# 12V_Buck_LDO_Power.net
KiCad netlist of a schematic drawn in Altium Designer
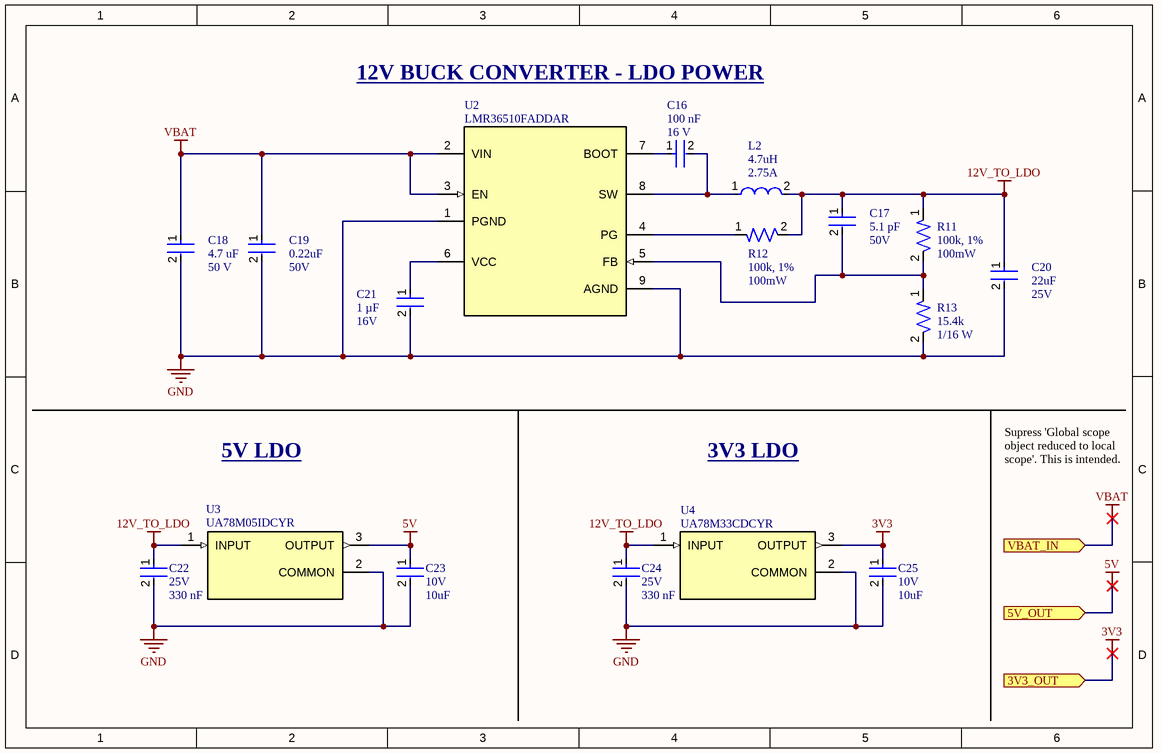
[diagram p0: 12V_Buck_LDO_Power.SchDoc]

(export (version "E")
  (design (tool "Eeschema 10.0.6"))
  (components
    (comp (ref "C16")
      (value "CC0402KRX7R7BB104")
      (footprint "FP-CC0402-IPC_B")
      (description "CAP CER 0.1UF 16V X7R 0402")
      (fields
        (field (name "MANUFACTURER") "YAGEO")
        (field (name "TOLERANCE") "0.1")
        (field (name "VOLTAGE RATING") "16 V")
        (field (name "CAPACITANCE") "100 nF")
      )
      (libsource (lib "JLC_25") (part "CAP-0.1U-0001"))
    )
    (comp (ref "C17")
      (value "CC0402CRNPO9BN5R1")
      (footprint "CAPC1005X55N")
      (description "5.1pF Â±0.25pF 50V Ceramic Capacitor C0G, NP0 0402 (1005 Metric)")
      (fields
        (field (name "MF") "Yageo")
        (field (name "VOLTAGE RATING") "50V")
        (field (name "CAPACITANCE") "5.1 pF")
      )
      (libsource (lib "JLC_25") (part "CAP-5.1P-0001"))
    )
    (comp (ref "C18")
      (value "CC0805KKX5R9BB475")
      (footprint "FP-CC0805-0_85-MFG")
      (description "CAP CER 4.7UF 50V X5R 0805")
      (fields
        (field (name "MANUFACTURER") "Yageo")
        (field (name "OCTOPART") "https://octopart.com/cc0805kkx5r9bb475-yageo-81932641")
        (field (name "VOLTAGE RATING") "50 V")
        (field (name "CAPACITANCE") "4.7 uF")
      )
      (libsource (lib "JLC_25") (part "CAP-4.7U-0002"))
    )
    (comp (ref "C19")
      (value "CC0603JRX7R9BB224")
      (footprint "CAP_CC0603_YAG")
      (description "0.22 µF ±5% 50V Ceramic Capacitor X7R 0603 (1608 Metric)")
      (fields (field (name "CAPACITANCE") "0.22uF") (field (name "VOLTAGE") "50V"))
      (libsource (lib "JLC_25") (part "CAP-0.22U-0001"))
    )
    (comp (ref "C20")
      (value "GRM32ER61E226KE15L")
      (footprint "FP-GRM32-MFG")
      (description "CAP CER 22UF 25V X5R 1210")
      (fields
        (field (name "TOLERANCE") "10%")
        (field (name "MANUFACTURER") "Murata Electronics North America")
        (field (name "VOLTAGE - RATED") "25V")
        (field (name "CAPACITANCE") "22uF")
      )
      (libsource (lib "JLC_25") (part "CAP-22U-0001"))
    )
    (comp (ref "C21")
      (value "CC0603KRX7R7BB105")
      (footprint "FP-CC0603-DA-MFG")
      (description "1 µF ±10% 16V Ceramic Capacitor X7R 0603 (1608 Metric)")
      (fields (field (name "CAPACITANCE") "1 µF") (field (name "VOLTAGE") "16V"))
      (libsource (lib "JLC_25") (part "CAP-1U-0002"))
    )
    (comp (ref "C22")
      (value "CC0603KRX7R8BB334")
      (footprint "FP-CC0603-DA-MFG")
      (description "CAP CER 0.33UF 25V X7R 0603")
      (fields
        (field (name "VOLTAGE") "25 V")
        (field (name "OCTOPART") "https://octopart.com/cc0603krx7r8bb334-yageo-47255252")
        (field (name "RATED VOLTAGE") "25V")
        (field (name "CAPACITANCE") "330 nF")
      )
      (libsource (lib "JLC_25") (part "CAP-0.33U-0001"))
    )
    (comp (ref "C23")
      (value "CC0603KRX5R6BB106")
      (footprint "FP-CC0603-DC-MFG")
      (description "CAP CER 10UF 10V X5R 0603")
      (fields
        (field (name "TOLERANCE") "10%")
        (field (name "RATED VOLTAGE") "10V")
        (field (name "CAPACITANCE") "10uF")
      )
      (libsource (lib "JLC_25") (part "CAP-10U-0001"))
    )
    (comp (ref "C24")
      (value "CC0603KRX7R8BB334")
      (footprint "FP-CC0603-DA-MFG")
      (description "CAP CER 0.33UF 25V X7R 0603")
      (fields
        (field (name "VOLTAGE") "25 V")
        (field (name "OCTOPART") "https://octopart.com/cc0603krx7r8bb334-yageo-47255252")
        (field (name "RATED VOLTAGE") "25V")
        (field (name "CAPACITANCE") "330 nF")
      )
      (libsource (lib "JLC_25") (part "CAP-0.33U-0001"))
    )
    (comp (ref "C25")
      (value "CC0603KRX5R6BB106")
      (footprint "FP-CC0603-DC-MFG")
      (description "CAP CER 10UF 10V X5R 0603")
      (fields
        (field (name "TOLERANCE") "10%")
        (field (name "RATED VOLTAGE") "10V")
        (field (name "CAPACITANCE") "10uF")
      )
      (libsource (lib "JLC_25") (part "CAP-10U-0001"))
    )
    (comp (ref "L2")
      (value "CDRH104NP-221MC")
      (description "FIXED IND 220UH 520MA 960MOHM SM")
      (fields (field (name "INDUCTANCE") "4.7uH") (field (name "CURRENT RATING") "2.75A"))
      (libsource (lib "JLC_25") (part "IND-4.7U-0001"))
    )
    (comp (ref "R11")
      (value "RC0603FR-07100KL")
      (footprint "FP-RC0603-0_55-IPC_B")
      (description "RES SMD 100K OHM 1% 1/10W 0603")
      (fields
        (field (name "TOLERANCE") "1%")
        (field (name "POWER") "100mW")
        (field (name "RESISTANCE") "100k, 1%")
      )
      (libsource (lib "JLC_25") (part "RES-100k-0001"))
    )
    (comp (ref "R12")
      (value "RC0603FR-07100KL")
      (footprint "FP-RC0603-0_55-IPC_B")
      (description "RES SMD 100K OHM 1% 1/10W 0603")
      (fields
        (field (name "TOLERANCE") "1%")
        (field (name "POWER") "100mW")
        (field (name "RESISTANCE") "100k, 1%")
      )
      (libsource (lib "JLC_25") (part "RES-100k-0001"))
    )
    (comp (ref "R13")
      (value "AC0402FR-0715K4L")
      (footprint "FP-AC0402-MFG")
      (description "RES 15.4kΩ ±1% 0.063W 0402")
      (fields
        (field (name "TOLERANCE") "1%")
        (field (name "POWER RATING") "1/16 W")
        (field (name "RESISTANCE") "15.4k")
      )
      (libsource (lib "JLC_25") (part "RES-15.4K-0001"))
    )
    (comp (ref "U2")
      (value "LMR36510FADDAR")
      (footprint "DDA0008J")
      (description "Buck Switching Regulator IC Positive Adjustable 1V 1 Output 1A 8-PowerSOIC (0.154\", 3.90mm Width)")
      (libsource (lib "JLC_25") (part "IC-BUCK-0003"))
    )
    (comp (ref "U3")
      (value "UA78M05IDCYR")
      (footprint "FP-DCY0004A-IPC_B")
      (description "IC REG LINEAR 5V 500MA SOT223-4")
      (fields
        (field (name "OCTOPART") "https://octopart.com/ua78m05idcyr-texas+instruments-525575")
        (field (name "MANUFACTURER") "Texas Instruments")
      )
      (libsource (lib "JLC_25") (part "IC-LDO-0001"))
    )
    (comp (ref "U4")
      (value "UA78M33CDCYR")
      (footprint "VREG_UA78M33CDCYR")
      (description "IC REG LIN 3.3V 500MA SOT223-4")
      (fields (field (name "MF") "Texas Instruments"))
      (libsource (lib "JLC_25") (part "IC-LDO-0002"))
    )
  )
  (nets
    (net (code "1") (name "3V3") (class "Default")
      (node (ref "C25") (pin "1") (pinfunction "1_1") (pintype "passive"))
      (node (ref "U4") (pin "3") (pinfunction "OUTPUT_3") (pintype "output"))
    )
    (net (code "2") (name "5V") (class "Default")
      (node (ref "C23") (pin "1") (pinfunction "1_1") (pintype "passive"))
      (node (ref "U3") (pin "3") (pinfunction "OUTPUT_3") (pintype "output"))
    )
    (net (code "3") (name "12V_TO_LDO") (class "Default")
      (node (ref "C17") (pin "1") (pinfunction "1_1") (pintype "passive"))
      (node (ref "C20") (pin "1") (pinfunction "1_1") (pintype "passive"))
      (node (ref "C22") (pin "1") (pinfunction "1_1") (pintype "passive"))
      (node (ref "C24") (pin "1") (pinfunction "1_1") (pintype "passive"))
      (node (ref "L2") (pin "2") (pinfunction "2_2") (pintype "passive"))
      (node (ref "R11") (pin "1") (pinfunction "1_1") (pintype "passive"))
      (node (ref "R12") (pin "2") (pinfunction "2_2") (pintype "passive"))
      (node (ref "U3") (pin "1") (pinfunction "INPUT_1") (pintype "input"))
      (node (ref "U4") (pin "1") (pinfunction "INPUT_1") (pintype "input"))
    )
    (net (code "4") (name "GND") (class "Default")
      (node (ref "C18") (pin "2") (pinfunction "2_2") (pintype "passive"))
      (node (ref "C19") (pin "2") (pinfunction "2_2") (pintype "passive"))
      (node (ref "C20") (pin "2") (pinfunction "2_2") (pintype "passive"))
      (node (ref "C21") (pin "2") (pinfunction "2_2") (pintype "passive"))
      (node (ref "C22") (pin "2") (pinfunction "2_2") (pintype "passive"))
      (node (ref "C23") (pin "2") (pinfunction "2_2") (pintype "passive"))
      (node (ref "C24") (pin "2") (pinfunction "2_2") (pintype "passive"))
      (node (ref "C25") (pin "2") (pinfunction "2_2") (pintype "passive"))
      (node (ref "R13") (pin "2") (pinfunction "2_2") (pintype "passive"))
      (node (ref "U2") (pin "1") (pinfunction "PGND_1") (pintype "power_in"))
      (node (ref "U2") (pin "9") (pinfunction "AGND_9") (pintype "passive"))
      (node (ref "U3") (pin "2") (pinfunction "COMMON_2") (pintype "passive"))
      (node (ref "U4") (pin "2") (pinfunction "COMMON_2") (pintype "power_in"))
    )
    (net (code "5") (name "Net-(U2-BOOT)") (class "Default")
      (node (ref "C16") (pin "1") (pinfunction "1_1") (pintype "passive"))
      (node (ref "U2") (pin "7") (pinfunction "BOOT_7") (pintype "power_in"))
    )
    (net (code "6") (name "Net-(U2-FB)") (class "Default")
      (node (ref "C17") (pin "2") (pinfunction "2_2") (pintype "passive"))
      (node (ref "R11") (pin "2") (pinfunction "2_2") (pintype "passive"))
      (node (ref "R13") (pin "1") (pinfunction "1_1") (pintype "passive"))
      (node (ref "U2") (pin "5") (pinfunction "FB_5") (pintype "input"))
    )
    (net (code "7") (name "Net-(U2-PG)") (class "Default")
      (node (ref "R12") (pin "1") (pinfunction "1_1") (pintype "passive"))
      (node (ref "U2") (pin "4") (pinfunction "PG_4") (pintype "open_collector"))
    )
    (net (code "8") (name "Net-(U2-SW)") (class "Default")
      (node (ref "C16") (pin "2") (pinfunction "2_2") (pintype "passive"))
      (node (ref "L2") (pin "1") (pinfunction "1_1") (pintype "passive"))
      (node (ref "U2") (pin "8") (pinfunction "SW_8") (pintype "power_in"))
    )
    (net (code "9") (name "Net-(U2-VCC)") (class "Default")
      (node (ref "C21") (pin "1") (pinfunction "1_1") (pintype "passive"))
      (node (ref "U2") (pin "6") (pinfunction "VCC_6") (pintype "power_in"))
    )
    (net (code "10") (name "VBAT") (class "Default")
      (node (ref "C18") (pin "1") (pinfunction "1_1") (pintype "passive"))
      (node (ref "C19") (pin "1") (pinfunction "1_1") (pintype "passive"))
      (node (ref "U2") (pin "2") (pinfunction "VIN_2") (pintype "power_in"))
      (node (ref "U2") (pin "3") (pinfunction "EN_3") (pintype "input"))
    )
  )
)
